# Communications_Board.net
KiCad netlist of a schematic drawn in Altium Designer
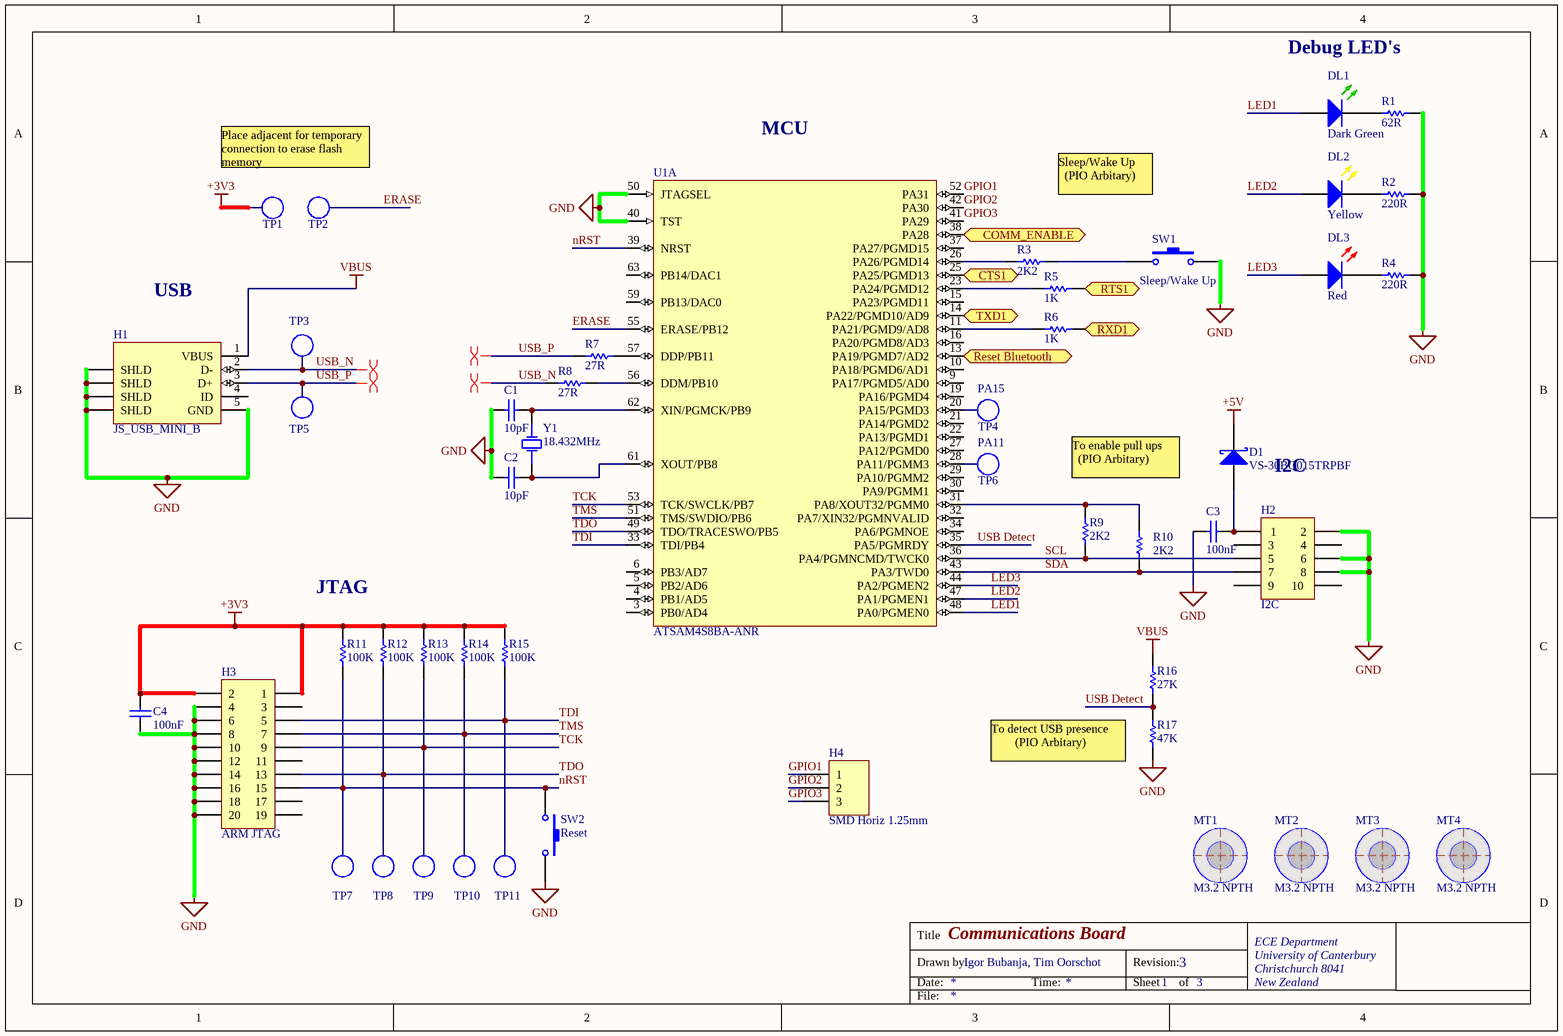
[diagram p0: Communications_Board.SchDoc]

(export (version "E")
  (design (tool "Eeschema 10.0.6"))
  (components
    (comp (ref "C1")
      (value "10pF")
      (footprint "CAPC1608L")
      (description "CAP CER 10pF COG/NPO 50V 0603")
      (libsource (lib "ECE Components_15_7") (part "CC_10pF_0603"))
    )
    (comp (ref "C2")
      (value "10pF")
      (footprint "CAPC1608L")
      (description "CAP CER 10pF COG/NPO 50V 0603")
      (libsource (lib "ECE Components_15_7") (part "CC_10pF_0603"))
    )
    (comp (ref "C3")
      (value "100nF")
      (footprint "CAPC1608L")
      (description "CAP CER 100nF X7R +-10% 50V 0603")
      (libsource (lib "ECE Components_15_7") (part "CC_100nF_0603"))
    )
    (comp (ref "C4")
      (value "100nF")
      (footprint "CAPC1608L")
      (description "CAP CER 100nF X7R +-10% 50V 0603")
      (libsource (lib "ECE Components_15_7") (part "CC_100nF_0603"))
    )
    (comp (ref "D1")
      (value "VS-30BQ015TRPBF")
      (footprint "SMC")
      (description "DIODE SCHOTTKY 15V 3A SMC")
      (fields
        (field (name "MANUFACTURER") "Vishay Semiconductor Diodes Division")
        (field (name "MANUFACTURER PART NUMBER") "VS-30BQ015TRPBF")
      )
      (libsource (lib "ECE Components_15_8") (part "DS_VS-30BQD015TRPBF"))
    )
    (comp (ref "DL1")
      (value "Dark Green")
      (footprint "WL-SMCW0603")
      (description "LED Dk Green 430mcd 0603 SMD")
      (fields
        (field (name "MANUFACTURER") "WURTH ELEKTRONIK")
        (field (name "MANUFACTURER PART NUMBER") "150060GS75000")
        (field (name "LED COLOUR") "Dark Green")
      )
      (libsource (lib "ECE Components_15_7") (part "DL_150060GS75000"))
    )
    (comp (ref "DL2")
      (value "Yellow")
      (footprint "WL-SMCW0603")
      (description "LED Yellow 120mcd 0603 SMD")
      (fields
        (field (name "MANUFACTURER") "WURTH ELEKTRONIK")
        (field (name "MANUFACTURER PART NUMBER") "150060YS75000")
        (field (name "LED COLOUR") "Yellow")
      )
      (libsource (lib "ECE Components_15_7") (part "DL_150060YS75000"))
    )
    (comp (ref "DL3")
      (value "Red")
      (footprint "WL-SMCW0603")
      (description "LED Red 250mcd 0603 SMD")
      (fields
        (field (name "MANUFACTURER") "WURTH ELEKTRONIK")
        (field (name "MANUFACTURER PART NUMBER") "150060RS75000")
        (field (name "LED COLOUR") "Red")
      )
      (libsource (lib "ECE Components_15_7") (part "DL_150060RS75000"))
    )
    (comp (ref "H1")
      (value "JS_USB_MINI_B")
      (footprint "USB/SM0.8-6H5")
      (description "USB 2.0, Right Angle, SMT, B Type, Receptacle, 5 Position,")
      (fields (field (name "MANUFACTURER") "FCI"))
      (libsource (lib "ECE Components_15_7") (part "JS_USB_MINI_B_SMT"))
    )
    (comp (ref "H2")
      (value "I2C")
      (footprint "188275-10")
      (description "IDC Header, 1,27mm, 10-Pin, Vert, SMT")
      (fields
        (field (name "MANUFACTURER") "TE Connectivity")
        (field (name "MANUFACTURER PART NUMBER") "1-188275-0")
      )
      (libsource (lib "ECE Components_15_7") (part "JB_HDR_IDC_5X2_VERT"))
    )
    (comp (ref "H3")
      (value "ARM JTAG")
      (footprint "188275-20")
      (description "IDC Header, 1,27mm, 20-Pin, Vert, SMT")
      (fields
        (field (name "MANUFACTURER") "TE Connectivity")
        (field (name "MANUFACTURER PART NUMBER") "2-188275-0")
      )
      (libsource (lib "ECE Components_15_7") (part "JB_HDR_IDC_10X2_VERT"))
    )
    (comp (ref "H4")
      (value "SMD Horiz 1.25mm")
      (footprint "SD-53261-0319")
      (description "Header_Horiz_3Pos_1.25mm_125V@1A_SMT")
      (fields (field (name "MANUFACTURER") "Molex") (field (name "MANUFACTURER PART NUMBER") "53261-0390"))
      (libsource (lib "ECE Components_15_8") (part "JB_53261-03"))
    )
    (comp (ref "MT1")
      (value "M3.2 NPTH")
      (footprint "MNT-HOLE_3.2mm_NPTH")
      (description "Fixing M3.2 Mount Hole NPTH")
      (fields (field (name "MANUFACTURER") "Hi-Q"))
      (libsource (lib "ECE Components_15_7") (part "MC_M3.2_HOLE"))
    )
    (comp (ref "MT2")
      (value "M3.2 NPTH")
      (footprint "MNT-HOLE_3.2mm_NPTH")
      (description "Fixing M3.2 Mount Hole NPTH")
      (fields (field (name "MANUFACTURER") "Hi-Q"))
      (libsource (lib "ECE Components_15_7") (part "MC_M3.2_HOLE"))
    )
    (comp (ref "MT3")
      (value "M3.2 NPTH")
      (footprint "MNT-HOLE_3.2mm_NPTH")
      (description "Fixing M3.2 Mount Hole NPTH")
      (fields (field (name "MANUFACTURER") "Hi-Q"))
      (libsource (lib "ECE Components_15_7") (part "MC_M3.2_HOLE"))
    )
    (comp (ref "MT4")
      (value "M3.2 NPTH")
      (footprint "MNT-HOLE_3.2mm_NPTH")
      (description "Fixing M3.2 Mount Hole NPTH")
      (fields (field (name "MANUFACTURER") "Hi-Q"))
      (libsource (lib "ECE Components_15_7") (part "MC_M3.2_HOLE"))
    )
    (comp (ref "R1")
      (value "62R")
      (footprint "RESC1608L")
      (description "RES 62 OHM 1/10W 5% 0603 SMD")
      (libsource (lib "ECE Components_15_7") (part "RS_62R"))
    )
    (comp (ref "R2")
      (value "220R")
      (footprint "RESC1608L")
      (description "RES 220 OHM 1/10W 5% 0603 SMD")
      (libsource (lib "ECE Components_15_7") (part "RS_220R"))
    )
    (comp (ref "R3")
      (value "2K2")
      (footprint "RESC1608L")
      (description "RES 2.2K OHM 1/10W 5% 0603 SMD")
      (libsource (lib "ECE Components_15_7") (part "RS_2K2"))
    )
    (comp (ref "R4")
      (value "220R")
      (footprint "RESC1608L")
      (description "RES 220 OHM 1/10W 5% 0603 SMD")
      (libsource (lib "ECE Components_15_7") (part "RS_220R"))
    )
    (comp (ref "R5")
      (value "1K")
      (footprint "RESC1608L")
      (description "RES 1.0K OHM 1/10W 5% 0603 SMD")
      (libsource (lib "ECE Components_15_8") (part "RS_1K"))
    )
    (comp (ref "R6")
      (value "1K")
      (footprint "RESC1608L")
      (description "RES 1.0K OHM 1/10W 5% 0603 SMD")
      (libsource (lib "ECE Components_15_8") (part "RS_1K"))
    )
    (comp (ref "R7")
      (value "27R")
      (footprint "RESC1608L")
      (description "RES 27 OHM 1/10W 5% 0603 SMD")
      (libsource (lib "ECE Components_15_7") (part "RS_27R"))
    )
    (comp (ref "R8")
      (value "27R")
      (footprint "RESC1608L")
      (description "RES 27 OHM 1/10W 5% 0603 SMD")
      (libsource (lib "ECE Components_15_7") (part "RS_27R"))
    )
    (comp (ref "R9")
      (value "2K2")
      (footprint "RESC1608L")
      (description "RES 2.2K OHM 1/10W 5% 0603 SMD")
      (libsource (lib "ECE Components_15_7") (part "RS_2K2"))
    )
    (comp (ref "R10")
      (value "2K2")
      (footprint "RESC1608L")
      (description "RES 2.2K OHM 1/10W 5% 0603 SMD")
      (libsource (lib "ECE Components_15_7") (part "RS_2K2"))
    )
    (comp (ref "R11")
      (value "100K")
      (footprint "RESC1608L")
      (description "RES 100K OHM 1/10W 5% 0603 SMD")
      (libsource (lib "ECE Components_15_7") (part "RS_100K"))
    )
    (comp (ref "R12")
      (value "100K")
      (footprint "RESC1608L")
      (description "RES 100K OHM 1/10W 5% 0603 SMD")
      (libsource (lib "ECE Components_15_7") (part "RS_100K"))
    )
    (comp (ref "R13")
      (value "100K")
      (footprint "RESC1608L")
      (description "RES 100K OHM 1/10W 5% 0603 SMD")
      (libsource (lib "ECE Components_15_7") (part "RS_100K"))
    )
    (comp (ref "R14")
      (value "100K")
      (footprint "RESC1608L")
      (description "RES 100K OHM 1/10W 5% 0603 SMD")
      (libsource (lib "ECE Components_15_7") (part "RS_100K"))
    )
    (comp (ref "R15")
      (value "100K")
      (footprint "RESC1608L")
      (description "RES 100K OHM 1/10W 5% 0603 SMD")
      (libsource (lib "ECE Components_15_7") (part "RS_100K"))
    )
    (comp (ref "R16")
      (value "27K")
      (footprint "RESC1608N")
      (description "RES 27K OHM 1/10W 5% 0603 SMD")
      (libsource (lib "ECE Components_15_7") (part "RS_27K"))
    )
    (comp (ref "R17")
      (value "47K")
      (footprint "RESC1608N")
      (description "RES 47.0K OHM 1/10W 5% 0603 SMD")
      (libsource (lib "ECE Components_15_7") (part "RS_47K"))
    )
    (comp (ref "SW1")
      (value "Sleep/Wake Up")
      (footprint "KSR211G")
      (description "SWITCH TACTILE SPST-NO SMD")
      (fields
        (field (name "MANUFACTURER") "C & K COMPONENTS")
        (field (name "MANUFACTURER PART NUMBER") "KSR211G LFS")
      )
      (libsource (lib "ECE Components_15_7") (part "WS_KSR211G LFS"))
    )
    (comp (ref "SW2")
      (value "Reset")
      (footprint "KSR211G")
      (description "SWITCH TACTILE SPST-NO SMD")
      (fields
        (field (name "MANUFACTURER") "C & K COMPONENTS")
        (field (name "MANUFACTURER PART NUMBER") "KSR211G LFS")
      )
      (libsource (lib "ECE Components_15_7") (part "WS_KSR211G LFS"))
    )
    (comp (ref "TP1")
      (value "3V3")
      (footprint "TP_0805")
      (description "Test Point 2.0X0.9X1.2mm SMD")
      (fields
        (field (name "MANUFACTURER") "TE Connectivity AMP Connectors")
        (field (name "MANUFACTURER PART NUMBER") "1625854-2")
      )
      (libsource (lib "ECE Components_15_7") (part "TP_0805"))
    )
    (comp (ref "TP2")
      (value "Erase")
      (footprint "TP_0805")
      (description "Test Point 2.0X0.9X1.2mm SMD")
      (fields
        (field (name "MANUFACTURER") "TE Connectivity AMP Connectors")
        (field (name "MANUFACTURER PART NUMBER") "1625854-2")
      )
      (libsource (lib "ECE Components_15_7") (part "TP_0805"))
    )
    (comp (ref "TP3")
      (value "USB_N")
      (footprint "TP_0805")
      (description "Test Point 2.0X0.9X1.2mm SMD")
      (fields
        (field (name "MANUFACTURER") "TE Connectivity AMP Connectors")
        (field (name "MANUFACTURER PART NUMBER") "1625854-2")
      )
      (libsource (lib "ECE Components_15_7") (part "TP_0805"))
    )
    (comp (ref "TP4")
      (value "PA15")
      (footprint "TP_0805")
      (description "Test Point 2.0X0.9X1.2mm SMD")
      (fields
        (field (name "MANUFACTURER") "TE Connectivity AMP Connectors")
        (field (name "MANUFACTURER PART NUMBER") "1625854-2")
      )
      (libsource (lib "ECE Components_15_7") (part "TP_0805"))
    )
    (comp (ref "TP5")
      (value "USB_P")
      (footprint "TP_0805")
      (description "Test Point 2.0X0.9X1.2mm SMD")
      (fields
        (field (name "MANUFACTURER") "TE Connectivity AMP Connectors")
        (field (name "MANUFACTURER PART NUMBER") "1625854-2")
      )
      (libsource (lib "ECE Components_15_7") (part "TP_0805"))
    )
    (comp (ref "TP6")
      (value "PA11")
      (footprint "TP_0805")
      (description "Test Point 2.0X0.9X1.2mm SMD")
      (fields
        (field (name "MANUFACTURER") "TE Connectivity AMP Connectors")
        (field (name "MANUFACTURER PART NUMBER") "1625854-2")
      )
      (libsource (lib "ECE Components_15_7") (part "TP_0805"))
    )
    (comp (ref "TP7")
      (value "nRST")
      (footprint "TP_0805")
      (description "Test Point 2.0X0.9X1.2mm SMD")
      (fields
        (field (name "MANUFACTURER") "TE Connectivity AMP Connectors")
        (field (name "MANUFACTURER PART NUMBER") "1625854-2")
      )
      (libsource (lib "ECE Components_15_7") (part "TP_0805"))
    )
    (comp (ref "TP8")
      (value "TDO")
      (footprint "TP_0805")
      (description "Test Point 2.0X0.9X1.2mm SMD")
      (fields
        (field (name "MANUFACTURER") "TE Connectivity AMP Connectors")
        (field (name "MANUFACTURER PART NUMBER") "1625854-2")
      )
      (libsource (lib "ECE Components_15_7") (part "TP_0805"))
    )
    (comp (ref "TP9")
      (value "TCK")
      (footprint "TP_0805")
      (description "Test Point 2.0X0.9X1.2mm SMD")
      (fields
        (field (name "MANUFACTURER") "TE Connectivity AMP Connectors")
        (field (name "MANUFACTURER PART NUMBER") "1625854-2")
      )
      (libsource (lib "ECE Components_15_7") (part "TP_0805"))
    )
    (comp (ref "TP10")
      (value "TMS")
      (footprint "TP_0805")
      (description "Test Point 2.0X0.9X1.2mm SMD")
      (fields
        (field (name "MANUFACTURER") "TE Connectivity AMP Connectors")
        (field (name "MANUFACTURER PART NUMBER") "1625854-2")
      )
      (libsource (lib "ECE Components_15_7") (part "TP_0805"))
    )
    (comp (ref "TP11")
      (value "TDI")
      (footprint "TP_0805")
      (description "Test Point 2.0X0.9X1.2mm SMD")
      (fields
        (field (name "MANUFACTURER") "TE Connectivity AMP Connectors")
        (field (name "MANUFACTURER PART NUMBER") "1625854-2")
      )
      (libsource (lib "ECE Components_15_7") (part "TP_0805"))
    )
    (comp (ref "U1")
      (value "ATSAM4S8BA-ANR")
      (footprint "LQFP64_L")
      (description "IC MCU 32BIT 512KB FLASH 64LQFP")
      (fields (field (name "MANUFACTURER") "Atmel"))
      (libsource (lib "ECE Components_15_7") (part "SE_ATSAM4S16BA-MU"))
    )
    (comp (ref "Y1")
      (value "18.432MHz")
      (footprint "6.0X3.5-4")
      (description "18.432 MHZ 4PF  6.0X3.5mm SMD")
      (fields
        (field (name "MANUFACTURER") "CTS-Frequency Controls")
        (field (name "MANUFACTURER PART NUMBER") "406C35B18M43200")
        (field (name "FREQUENCY") "18.432MHz")
      )
      (libsource (lib "ECE Components_15_7") (part "XT_CRYSTAL_18.432MHz_13pF"))
    )
  )
  (nets
    (net (code "1") (name "+3V3") (class "Default")
      (node (ref "C4") (pin "2") (pinfunction "2_2") (pintype "passive"))
      (node (ref "H3") (pin "1") (pinfunction "1_1") (pintype "passive"))
      (node (ref "H3") (pin "2") (pinfunction "2_2") (pintype "passive"))
      (node (ref "R11") (pin "2") (pinfunction "2_2") (pintype "passive"))
      (node (ref "R12") (pin "2") (pinfunction "2_2") (pintype "passive"))
      (node (ref "R13") (pin "2") (pinfunction "2_2") (pintype "passive"))
      (node (ref "R14") (pin "2") (pinfunction "2_2") (pintype "passive"))
      (node (ref "R15") (pin "2") (pinfunction "2_2") (pintype "passive"))
      (node (ref "TP1") (pin "1") (pinfunction "TP_1") (pintype "passive"))
    )
    (net (code "2") (name "+5V") (class "Default")
      (node (ref "D1") (pin "2") (pinfunction "K_2") (pintype "passive"))
    )
    (net (code "3") (name "/COMM_ENABLE") (class "Default")
      (node (ref "U1") (pin "38") (pinfunction "PA28_38") (pintype "bidirectional"))
    )
    (net (code "4") (name "/CTS1") (class "Default")
      (node (ref "U1") (pin "25") (pinfunction "PA25/PGMD13_25") (pintype "bidirectional"))
    )
    (net (code "5") (name "/ERASE") (class "Default")
      (node (ref "TP2") (pin "1") (pinfunction "TP_1") (pintype "passive"))
      (node (ref "U1") (pin "55") (pinfunction "ERASE/PB12_55") (pintype "bidirectional"))
    )
    (net (code "6") (name "/GPIO1") (class "Default")
      (node (ref "H4") (pin "1") (pinfunction "1_1") (pintype "passive"))
      (node (ref "U1") (pin "52") (pinfunction "PA31_52") (pintype "bidirectional"))
    )
    (net (code "7") (name "/GPIO2") (class "Default")
      (node (ref "H4") (pin "2") (pinfunction "2_2") (pintype "passive"))
      (node (ref "U1") (pin "42") (pinfunction "PA30_42") (pintype "bidirectional"))
    )
    (net (code "8") (name "/GPIO3") (class "Default")
      (node (ref "H4") (pin "3") (pinfunction "3_3") (pintype "passive"))
      (node (ref "U1") (pin "41") (pinfunction "PA29_41") (pintype "bidirectional"))
    )
    (net (code "9") (name "/LED1") (class "Default")
      (node (ref "DL1") (pin "2") (pinfunction "A_2") (pintype "passive"))
      (node (ref "U1") (pin "48") (pinfunction "PA0/PGMEN0_48") (pintype "bidirectional"))
    )
    (net (code "10") (name "/LED2") (class "Default")
      (node (ref "DL2") (pin "2") (pinfunction "A_2") (pintype "passive"))
      (node (ref "U1") (pin "47") (pinfunction "PA1/PGMEN1_47") (pintype "bidirectional"))
    )
    (net (code "11") (name "/LED3") (class "Default")
      (node (ref "DL3") (pin "2") (pinfunction "A_2") (pintype "passive"))
      (node (ref "U1") (pin "44") (pinfunction "PA2/PGMEN2_44") (pintype "bidirectional"))
    )
    (net (code "12") (name "/RTS1") (class "Default")
      (node (ref "R5") (pin "2") (pinfunction "2_2") (pintype "passive"))
    )
    (net (code "13") (name "/RXD1") (class "Default")
      (node (ref "R6") (pin "2") (pinfunction "2_2") (pintype "passive"))
    )
    (net (code "14") (name "/Reset Bluetooth") (class "Default")
      (node (ref "U1") (pin "13") (pinfunction "PA19/PGMD7/AD2_13") (pintype "bidirectional"))
    )
    (net (code "15") (name "/SCL") (class "Default")
      (node (ref "H2") (pin "5") (pinfunction "5_5") (pintype "passive"))
      (node (ref "R9") (pin "1") (pinfunction "1_1") (pintype "passive"))
      (node (ref "U1") (pin "36") (pinfunction "PA4/PGMNCMD/TWCK0_36") (pintype "bidirectional"))
    )
    (net (code "16") (name "/SDA") (class "Default")
      (node (ref "H2") (pin "7") (pinfunction "7_7") (pintype "passive"))
      (node (ref "R10") (pin "1") (pinfunction "1_1") (pintype "passive"))
      (node (ref "U1") (pin "43") (pinfunction "PA3/TWD0_43") (pintype "bidirectional"))
    )
    (net (code "17") (name "/TCK") (class "Default")
      (node (ref "H3") (pin "9") (pinfunction "9_9") (pintype "passive"))
      (node (ref "R13") (pin "1") (pinfunction "1_1") (pintype "passive"))
      (node (ref "TP9") (pin "1") (pinfunction "TP_1") (pintype "passive"))
      (node (ref "U1") (pin "53") (pinfunction "TCK/SWCLK/PB7_53") (pintype "bidirectional"))
    )
    (net (code "18") (name "/TDI") (class "Default")
      (node (ref "H3") (pin "5") (pinfunction "5_5") (pintype "passive"))
      (node (ref "R15") (pin "1") (pinfunction "1_1") (pintype "passive"))
      (node (ref "TP11") (pin "1") (pinfunction "TP_1") (pintype "passive"))
      (node (ref "U1") (pin "33") (pinfunction "TDI/PB4_33") (pintype "bidirectional"))
    )
    (net (code "19") (name "/TDO") (class "Default")
      (node (ref "H3") (pin "13") (pinfunction "13_13") (pintype "passive"))
      (node (ref "R12") (pin "1") (pinfunction "1_1") (pintype "passive"))
      (node (ref "TP8") (pin "1") (pinfunction "TP_1") (pintype "passive"))
      (node (ref "U1") (pin "49") (pinfunction "TDO/TRACESWO/PB5_49") (pintype "bidirectional"))
    )
    (net (code "20") (name "/TMS") (class "Default")
      (node (ref "H3") (pin "7") (pinfunction "7_7") (pintype "passive"))
      (node (ref "R14") (pin "1") (pinfunction "1_1") (pintype "passive"))
      (node (ref "TP10") (pin "1") (pinfunction "TP_1") (pintype "passive"))
      (node (ref "U1") (pin "51") (pinfunction "TMS/SWDIO/PB6_51") (pintype "bidirectional"))
    )
    (net (code "21") (name "/TXD1") (class "Default")
      (node (ref "U1") (pin "14") (pinfunction "PA22/PGMD10/AD9_14") (pintype "bidirectional"))
    )
    (net (code "22") (name "/USB Detect") (class "Default")
      (node (ref "R16") (pin "1") (pinfunction "1_1") (pintype "passive"))
      (node (ref "R17") (pin "2") (pinfunction "2_2") (pintype "passive"))
      (node (ref "U1") (pin "35") (pinfunction "PA5/PGMRDY_35") (pintype "bidirectional"))
    )
    (net (code "23") (name "/USB_N") (class "Default")
      (node (ref "H1") (pin "2") (pinfunction "D-_2") (pintype "bidirectional"))
      (node (ref "R8") (pin "1") (pinfunction "1_1") (pintype "passive"))
      (node (ref "TP3") (pin "1") (pinfunction "TP_1") (pintype "passive"))
    )
    (net (code "24") (name "/USB_P") (class "Default")
      (node (ref "H1") (pin "3") (pinfunction "D+_3") (pintype "bidirectional"))
      (node (ref "R7") (pin "1") (pinfunction "1_1") (pintype "passive"))
      (node (ref "TP5") (pin "1") (pinfunction "TP_1") (pintype "passive"))
    )
    (net (code "25") (name "/nRST") (class "Default")
      (node (ref "H3") (pin "15") (pinfunction "15_15") (pintype "passive"))
      (node (ref "R11") (pin "1") (pinfunction "1_1") (pintype "passive"))
      (node (ref "SW2") (pin "1") (pintype "passive"))
      (node (ref "TP7") (pin "1") (pinfunction "TP_1") (pintype "passive"))
      (node (ref "U1") (pin "39") (pinfunction "NRST_39") (pintype "bidirectional"))
    )
    (net (code "26") (name "GND") (class "Default")
      (node (ref "C1") (pin "1") (pinfunction "1_1") (pintype "passive"))
      (node (ref "C2") (pin "1") (pinfunction "1_1") (pintype "passive"))
      (node (ref "C3") (pin "1") (pinfunction "1_1") (pintype "passive"))
      (node (ref "C4") (pin "1") (pinfunction "1_1") (pintype "passive"))
      (node (ref "H1") (pin "5") (pinfunction "GND_5") (pintype "passive"))
      (node (ref "H1") (pin "6") (pinfunction "SHLD_6") (pintype "passive"))
      (node (ref "H1") (pin "7") (pinfunction "SHLD_7") (pintype "passive"))
      (node (ref "H1") (pin "8") (pinfunction "SHLD_8") (pintype "passive"))
      (node (ref "H1") (pin "9") (pinfunction "SHLD_9") (pintype "passive"))
      (node (ref "H2") (pin "2") (pinfunction "2_2") (pintype "passive"))
      (node (ref "H2") (pin "6") (pinfunction "6_6") (pintype "passive"))
      (node (ref "H2") (pin "8") (pinfunction "8_8") (pintype "passive"))
      (node (ref "H3") (pin "10") (pinfunction "10_10") (pintype "passive"))
      (node (ref "H3") (pin "12") (pinfunction "12_12") (pintype "passive"))
      (node (ref "H3") (pin "14") (pinfunction "14_14") (pintype "passive"))
      (node (ref "H3") (pin "16") (pinfunction "16_16") (pintype "passive"))
      (node (ref "H3") (pin "18") (pinfunction "18_18") (pintype "passive"))
      (node (ref "H3") (pin "20") (pinfunction "20_20") (pintype "passive"))
      (node (ref "H3") (pin "4") (pinfunction "4_4") (pintype "passive"))
      (node (ref "H3") (pin "6") (pinfunction "6_6") (pintype "passive"))
      (node (ref "H3") (pin "8") (pinfunction "8_8") (pintype "passive"))
      (node (ref "R1") (pin "2") (pinfunction "2_2") (pintype "passive"))
      (node (ref "R17") (pin "1") (pinfunction "1_1") (pintype "passive"))
      (node (ref "R2") (pin "2") (pinfunction "2_2") (pintype "passive"))
      (node (ref "R4") (pin "2") (pinfunction "2_2") (pintype "passive"))
      (node (ref "SW1") (pin "2") (pintype "passive"))
      (node (ref "SW2") (pin "2") (pintype "passive"))
      (node (ref "U1") (pin "40") (pinfunction "TST_40") (pintype "input"))
      (node (ref "U1") (pin "50") (pinfunction "JTAGSEL_50") (pintype "input"))
    )
    (net (code "27") (name "Net-(D1-A)") (class "Default")
      (node (ref "C3") (pin "2") (pinfunction "2_2") (pintype "passive"))
      (node (ref "D1") (pin "1") (pinfunction "A_1") (pintype "passive"))
      (node (ref "H2") (pin "1") (pinfunction "1_1") (pintype "passive"))
    )
    (net (code "28") (name "Net-(DL1-K)") (class "Default")
      (node (ref "DL1") (pin "1") (pinfunction "K_1") (pintype "passive"))
      (node (ref "R1") (pin "1") (pinfunction "1_1") (pintype "passive"))
    )
    (net (code "29") (name "Net-(DL2-K)") (class "Default")
      (node (ref "DL2") (pin "1") (pinfunction "K_1") (pintype "passive"))
      (node (ref "R2") (pin "1") (pinfunction "1_1") (pintype "passive"))
    )
    (net (code "30") (name "Net-(DL3-K)") (class "Default")
      (node (ref "DL3") (pin "1") (pinfunction "K_1") (pintype "passive"))
      (node (ref "R4") (pin "1") (pinfunction "1_1") (pintype "passive"))
    )
    (net (code "31") (name "Net-(R3-Pad2)") (class "Default")
      (node (ref "R3") (pin "2") (pinfunction "2_2") (pintype "passive"))
      (node (ref "SW1") (pin "1") (pintype "passive"))
    )
    (net (code "32") (name "Net-(TP4-TP)") (class "Default")
      (node (ref "TP4") (pin "1") (pinfunction "TP_1") (pintype "passive"))
      (node (ref "U1") (pin "20") (pinfunction "PA15/PGMD3_20") (pintype "bidirectional"))
    )
    (net (code "33") (name "Net-(TP6-TP)") (class "Default")
      (node (ref "TP6") (pin "1") (pinfunction "TP_1") (pintype "passive"))
      (node (ref "U1") (pin "28") (pinfunction "PA11/PGMM3_28") (pintype "bidirectional"))
    )
    (net (code "34") (name "Net-(U1A-DDM{slash}PB10)") (class "Default")
      (node (ref "R8") (pin "2") (pinfunction "2_2") (pintype "passive"))
      (node (ref "U1") (pin "56") (pinfunction "DDM/PB10_56") (pintype "bidirectional"))
    )
    (net (code "35") (name "Net-(U1A-DDP{slash}PB11)") (class "Default")
      (node (ref "R7") (pin "2") (pinfunction "2_2") (pintype "passive"))
      (node (ref "U1") (pin "57") (pinfunction "DDP/PB11_57") (pintype "bidirectional"))
    )
    (net (code "36") (name "Net-(U1A-PA8{slash}XOUT32{slash}PGMM0)") (class "Default")
      (node (ref "R10") (pin "2") (pinfunction "2_2") (pintype "passive"))
      (node (ref "R9") (pin "2") (pinfunction "2_2") (pintype "passive"))
      (node (ref "U1") (pin "31") (pinfunction "PA8/XOUT32/PGMM0_31") (pintype "bidirectional"))
    )
    (net (code "37") (name "Net-(U1A-PA21{slash}PGMD9{slash}AD8)") (class "Default")
      (node (ref "R6") (pin "1") (pinfunction "1_1") (pintype "passive"))
      (node (ref "U1") (pin "11") (pinfunction "PA21/PGMD9/AD8_11") (pintype "bidirectional"))
    )
    (net (code "38") (name "Net-(U1A-PA24{slash}PGMD12)") (class "Default")
      (node (ref "R5") (pin "1") (pinfunction "1_1") (pintype "passive"))
      (node (ref "U1") (pin "23") (pinfunction "PA24/PGMD12_23") (pintype "bidirectional"))
    )
    (net (code "39") (name "Net-(U1A-PA26{slash}PGMD14)") (class "Default")
      (node (ref "R3") (pin "1") (pinfunction "1_1") (pintype "passive"))
      (node (ref "U1") (pin "26") (pinfunction "PA26/PGMD14_26") (pintype "bidirectional"))
    )
    (net (code "40") (name "Net-(U1A-XIN{slash}PGMCK{slash}PB9)") (class "Default")
      (node (ref "C1") (pin "2") (pinfunction "2_2") (pintype "passive"))
      (node (ref "U1") (pin "62") (pinfunction "XIN/PGMCK/PB9_62") (pintype "bidirectional"))
      (node (ref "Y1") (pin "3") (pinfunction "OSC2_3") (pintype "passive"))
    )
    (net (code "41") (name "Net-(U1A-XOUT{slash}PB8)") (class "Default")
      (node (ref "C2") (pin "2") (pinfunction "2_2") (pintype "passive"))
      (node (ref "U1") (pin "61") (pinfunction "XOUT/PB8_61") (pintype "bidirectional"))
      (node (ref "Y1") (pin "1") (pinfunction "OSC1_1") (pintype "passive"))
    )
    (net (code "42") (name "VBUS") (class "Default")
      (node (ref "H1") (pin "1") (pinfunction "VBUS_1") (pintype "power_in"))
      (node (ref "R16") (pin "2") (pinfunction "2_2") (pintype "passive"))
    )
    (net (code "43") (name "unconnected-(H1-ID-Pad4)") (class "Default")
      (node (ref "H1") (pin "4") (pinfunction "ID_4") (pintype "power_in"))
    )
    (net (code "44") (name "unconnected-(H2-Pad3)") (class "Default")
      (node (ref "H2") (pin "3") (pinfunction "3_3") (pintype "passive"))
    )
    (net (code "45") (name "unconnected-(H2-Pad4)") (class "Default")
      (node (ref "H2") (pin "4") (pinfunction "4_4") (pintype "passive"))
    )
    (net (code "46") (name "unconnected-(H2-Pad9)") (class "Default")
      (node (ref "H2") (pin "9") (pinfunction "9_9") (pintype "passive"))
    )
    (net (code "47") (name "unconnected-(H2-Pad10)") (class "Default")
      (node (ref "H2") (pin "10") (pinfunction "10_10") (pintype "passive"))
    )
    (net (code "48") (name "unconnected-(H3-Pad3)") (class "Default")
      (node (ref "H3") (pin "3") (pinfunction "3_3") (pintype "passive"))
    )
    (net (code "49") (name "unconnected-(H3-Pad11)") (class "Default")
      (node (ref "H3") (pin "11") (pinfunction "11_11") (pintype "passive"))
    )
    (net (code "50") (name "unconnected-(H3-Pad17)") (class "Default")
      (node (ref "H3") (pin "17") (pinfunction "17_17") (pintype "passive"))
    )
    (net (code "51") (name "unconnected-(H3-Pad19)") (class "Default")
      (node (ref "H3") (pin "19") (pinfunction "19_19") (pintype "passive"))
    )
    (net (code "52") (name "unconnected-(U1A-PA6{slash}PGMNOE-Pad34)") (class "Default")
      (node (ref "U1") (pin "34") (pinfunction "PA6/PGMNOE_34") (pintype "bidirectional"))
    )
    (net (code "53") (name "unconnected-(U1A-PA7{slash}XIN32{slash}PGMNVALID-Pad32)") (class "Default")
      (node (ref "U1") (pin "32") (pinfunction "PA7/XIN32/PGMNVALID_32") (pintype "bidirectional"))
    )
    (net (code "54") (name "unconnected-(U1A-PA9{slash}PGMM1-Pad30)") (class "Default")
      (node (ref "U1") (pin "30") (pinfunction "PA9/PGMM1_30") (pintype "bidirectional"))
    )
    (net (code "55") (name "unconnected-(U1A-PA10{slash}PGMM2-Pad29)") (class "Default")
      (node (ref "U1") (pin "29") (pinfunction "PA10/PGMM2_29") (pintype "bidirectional"))
    )
    (net (code "56") (name "unconnected-(U1A-PA12{slash}PGMD0-Pad27)") (class "Default")
      (node (ref "U1") (pin "27") (pinfunction "PA12/PGMD0_27") (pintype "bidirectional"))
    )
    (net (code "57") (name "unconnected-(U1A-PA13{slash}PGMD1-Pad22)") (class "Default")
      (node (ref "U1") (pin "22") (pinfunction "PA13/PGMD1_22") (pintype "bidirectional"))
    )
    (net (code "58") (name "unconnected-(U1A-PA14{slash}PGMD2-Pad21)") (class "Default")
      (node (ref "U1") (pin "21") (pinfunction "PA14/PGMD2_21") (pintype "bidirectional"))
    )
    (net (code "59") (name "unconnected-(U1A-PA16{slash}PGMD4-Pad19)") (class "Default")
      (node (ref "U1") (pin "19") (pinfunction "PA16/PGMD4_19") (pintype "bidirectional"))
    )
    (net (code "60") (name "unconnected-(U1A-PA17{slash}PGMD5{slash}AD0-Pad9)") (class "Default")
      (node (ref "U1") (pin "9") (pinfunction "PA17/PGMD5/AD0_9") (pintype "bidirectional"))
    )
    (net (code "61") (name "unconnected-(U1A-PA18{slash}PGMD6{slash}AD1-Pad10)") (class "Default")
      (node (ref "U1") (pin "10") (pinfunction "PA18/PGMD6/AD1_10") (pintype "bidirectional"))
    )
    (net (code "62") (name "unconnected-(U1A-PA20{slash}PGMD8{slash}AD3-Pad16)") (class "Default")
      (node (ref "U1") (pin "16") (pinfunction "PA20/PGMD8/AD3_16") (pintype "bidirectional"))
    )
    (net (code "63") (name "unconnected-(U1A-PA23{slash}PGMD11-Pad15)") (class "Default")
      (node (ref "U1") (pin "15") (pinfunction "PA23/PGMD11_15") (pintype "bidirectional"))
    )
    (net (code "64") (name "unconnected-(U1A-PA27{slash}PGMD15-Pad37)") (class "Default")
      (node (ref "U1") (pin "37") (pinfunction "PA27/PGMD15_37") (pintype "bidirectional"))
    )
    (net (code "65") (name "unconnected-(U1A-PB0{slash}AD4-Pad3)") (class "Default")
      (node (ref "U1") (pin "3") (pinfunction "PB0/AD4_3") (pintype "bidirectional"))
    )
    (net (code "66") (name "unconnected-(U1A-PB1{slash}AD5-Pad4)") (class "Default")
      (node (ref "U1") (pin "4") (pinfunction "PB1/AD5_4") (pintype "bidirectional"))
    )
    (net (code "67") (name "unconnected-(U1A-PB2{slash}AD6-Pad5)") (class "Default")
      (node (ref "U1") (pin "5") (pinfunction "PB2/AD6_5") (pintype "bidirectional"))
    )
    (net (code "68") (name "unconnected-(U1A-PB3{slash}AD7-Pad6)") (class "Default")
      (node (ref "U1") (pin "6") (pinfunction "PB3/AD7_6") (pintype "bidirectional"))
    )
    (net (code "69") (name "unconnected-(U1A-PB13{slash}DAC0-Pad59)") (class "Default")
      (node (ref "U1") (pin "59") (pinfunction "PB13/DAC0_59") (pintype "bidirectional"))
    )
    (net (code "70") (name "unconnected-(U1A-PB14{slash}DAC1-Pad63)") (class "Default")
      (node (ref "U1") (pin "63") (pinfunction "PB14/DAC1_63") (pintype "bidirectional"))
    )
  )
)
